# mbed-WiFi-Cloud-v1_0_0.net
KiCad netlist of a schematic drawn in EAGLE
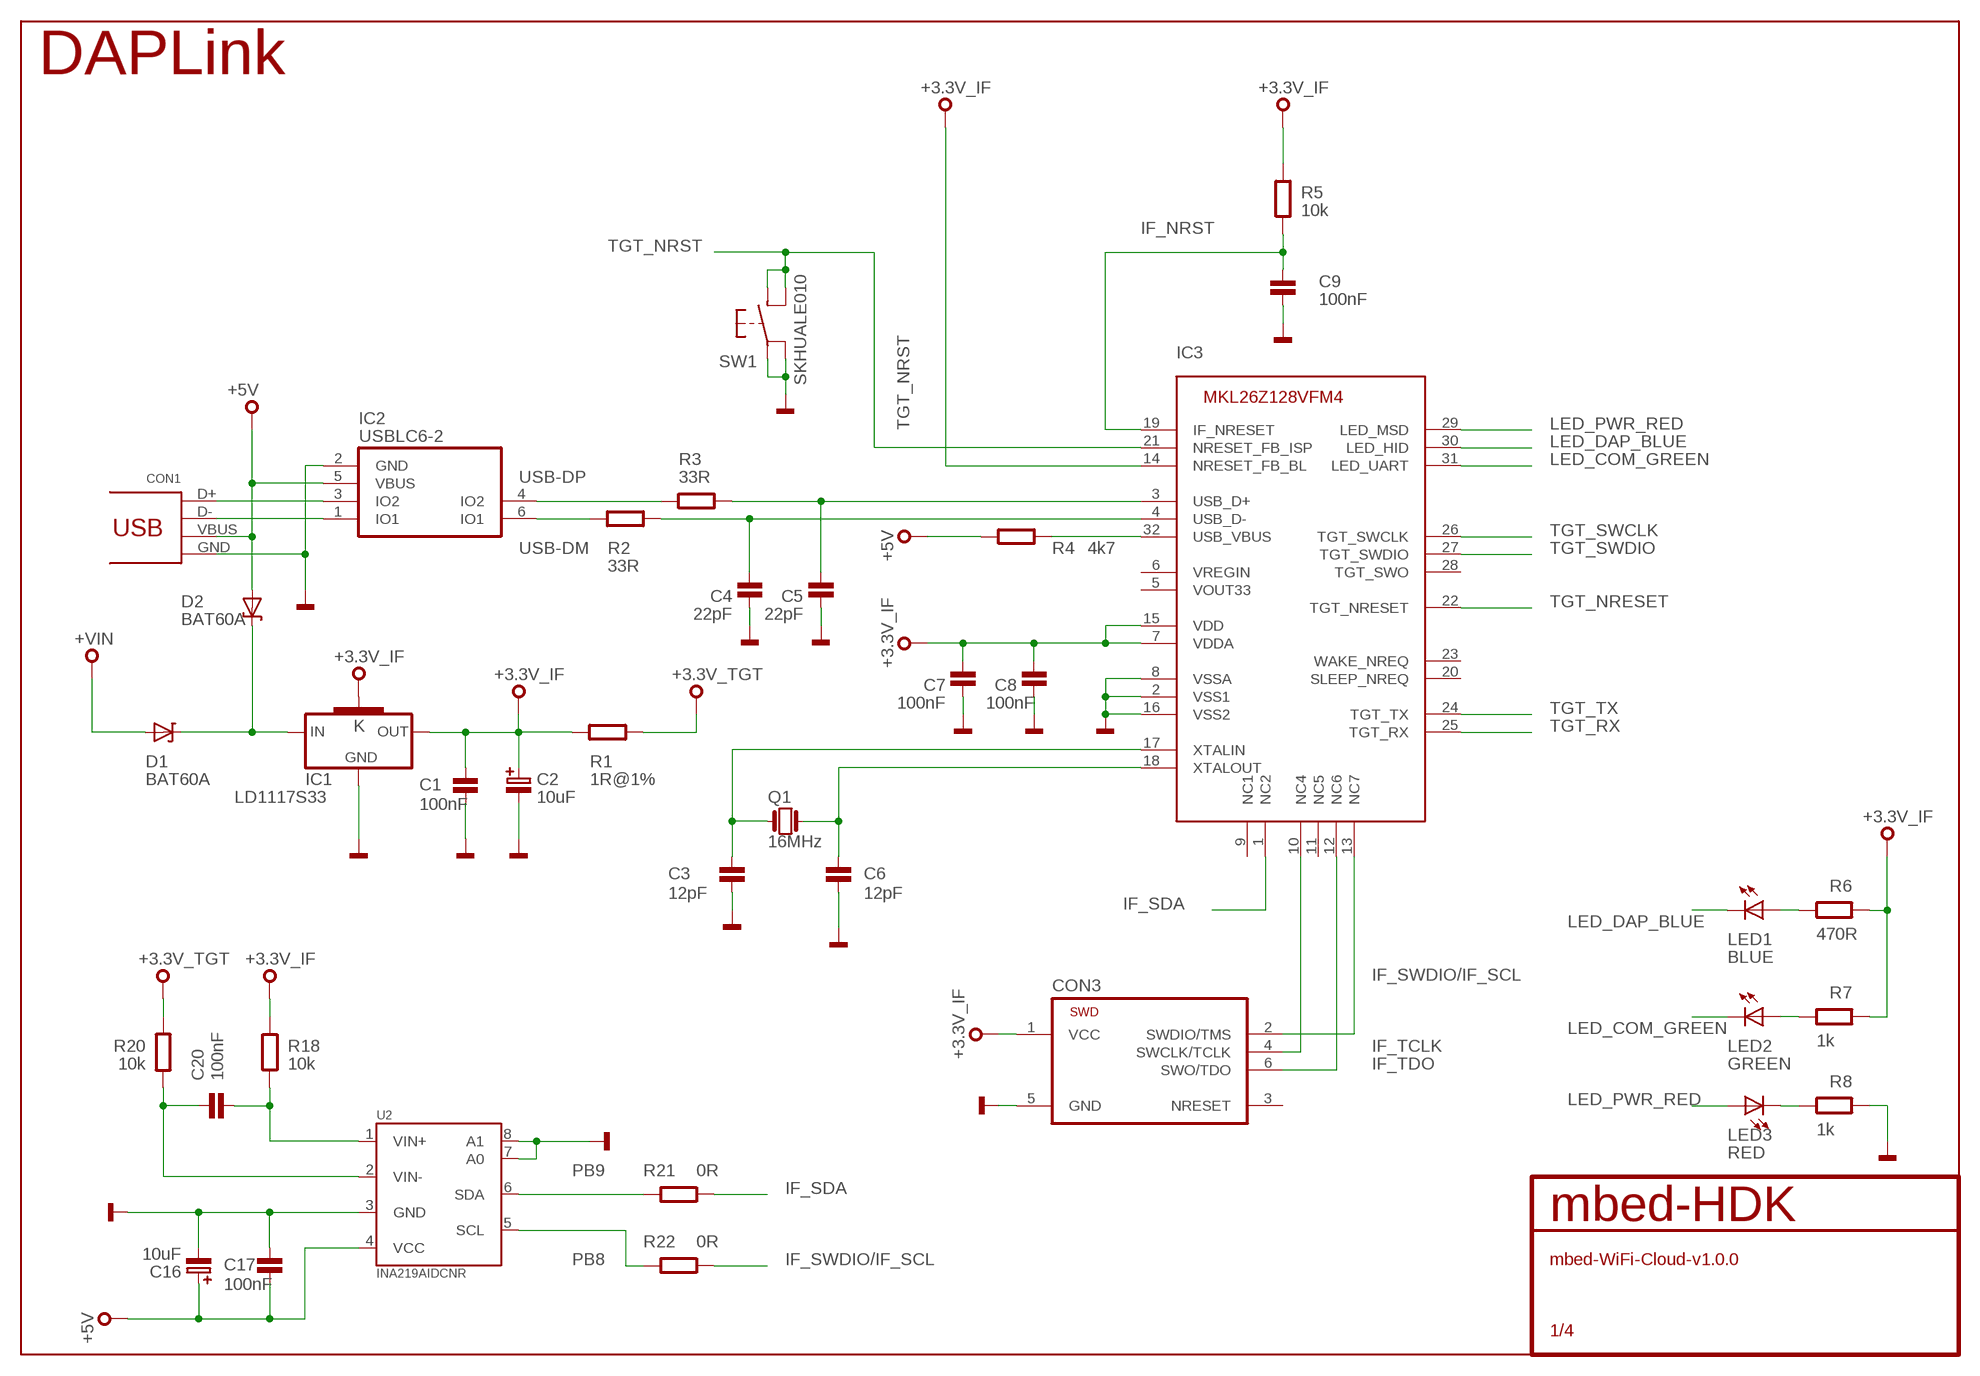
[diagram p0: schematic, sheet 1]
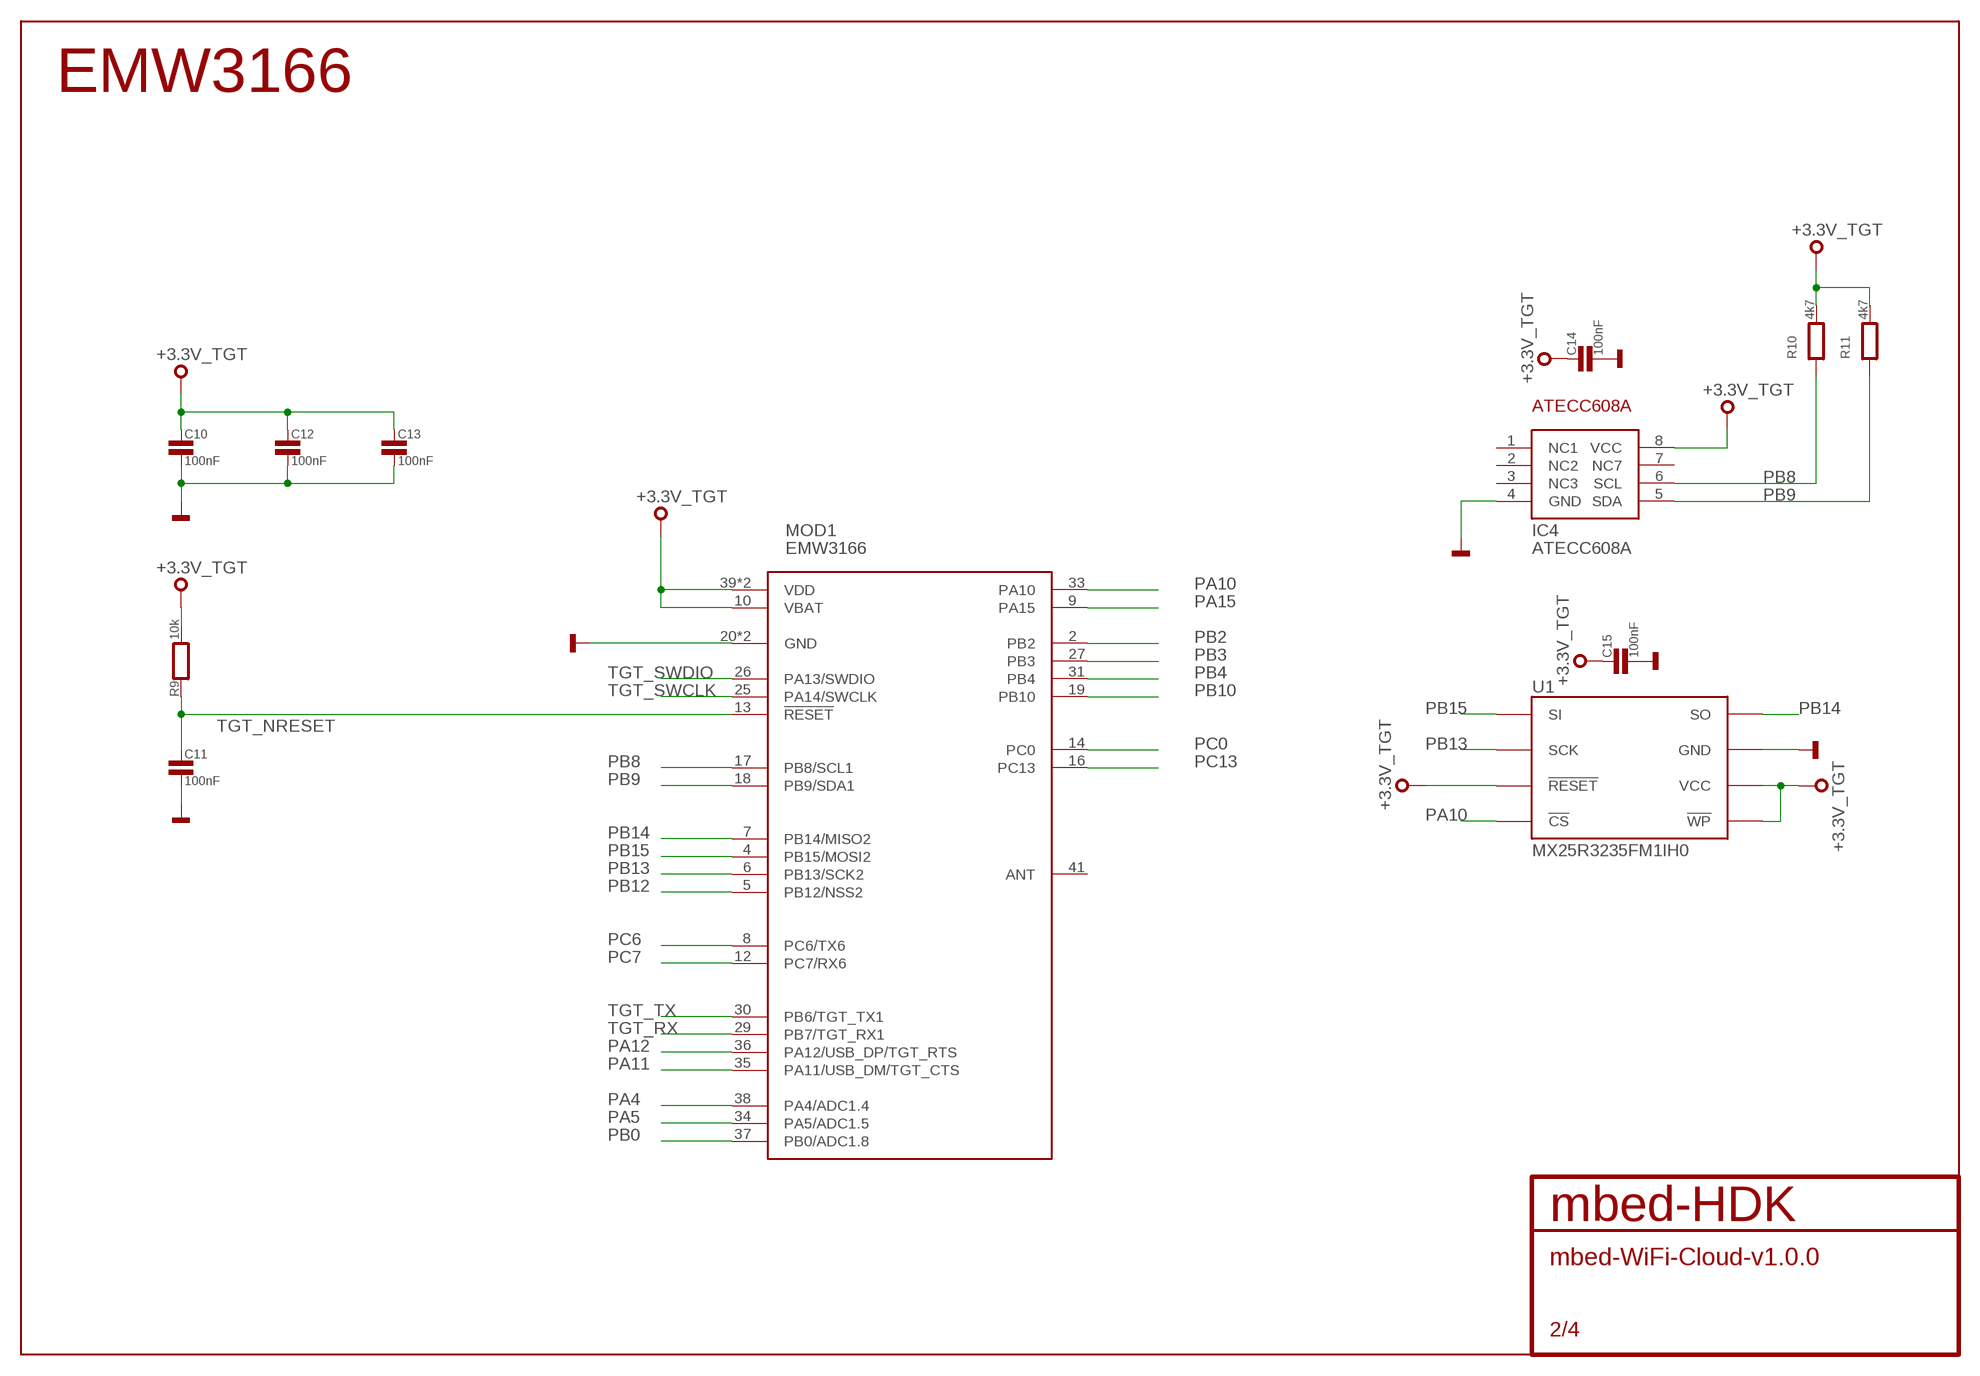
[diagram p1: schematic, sheet 2]
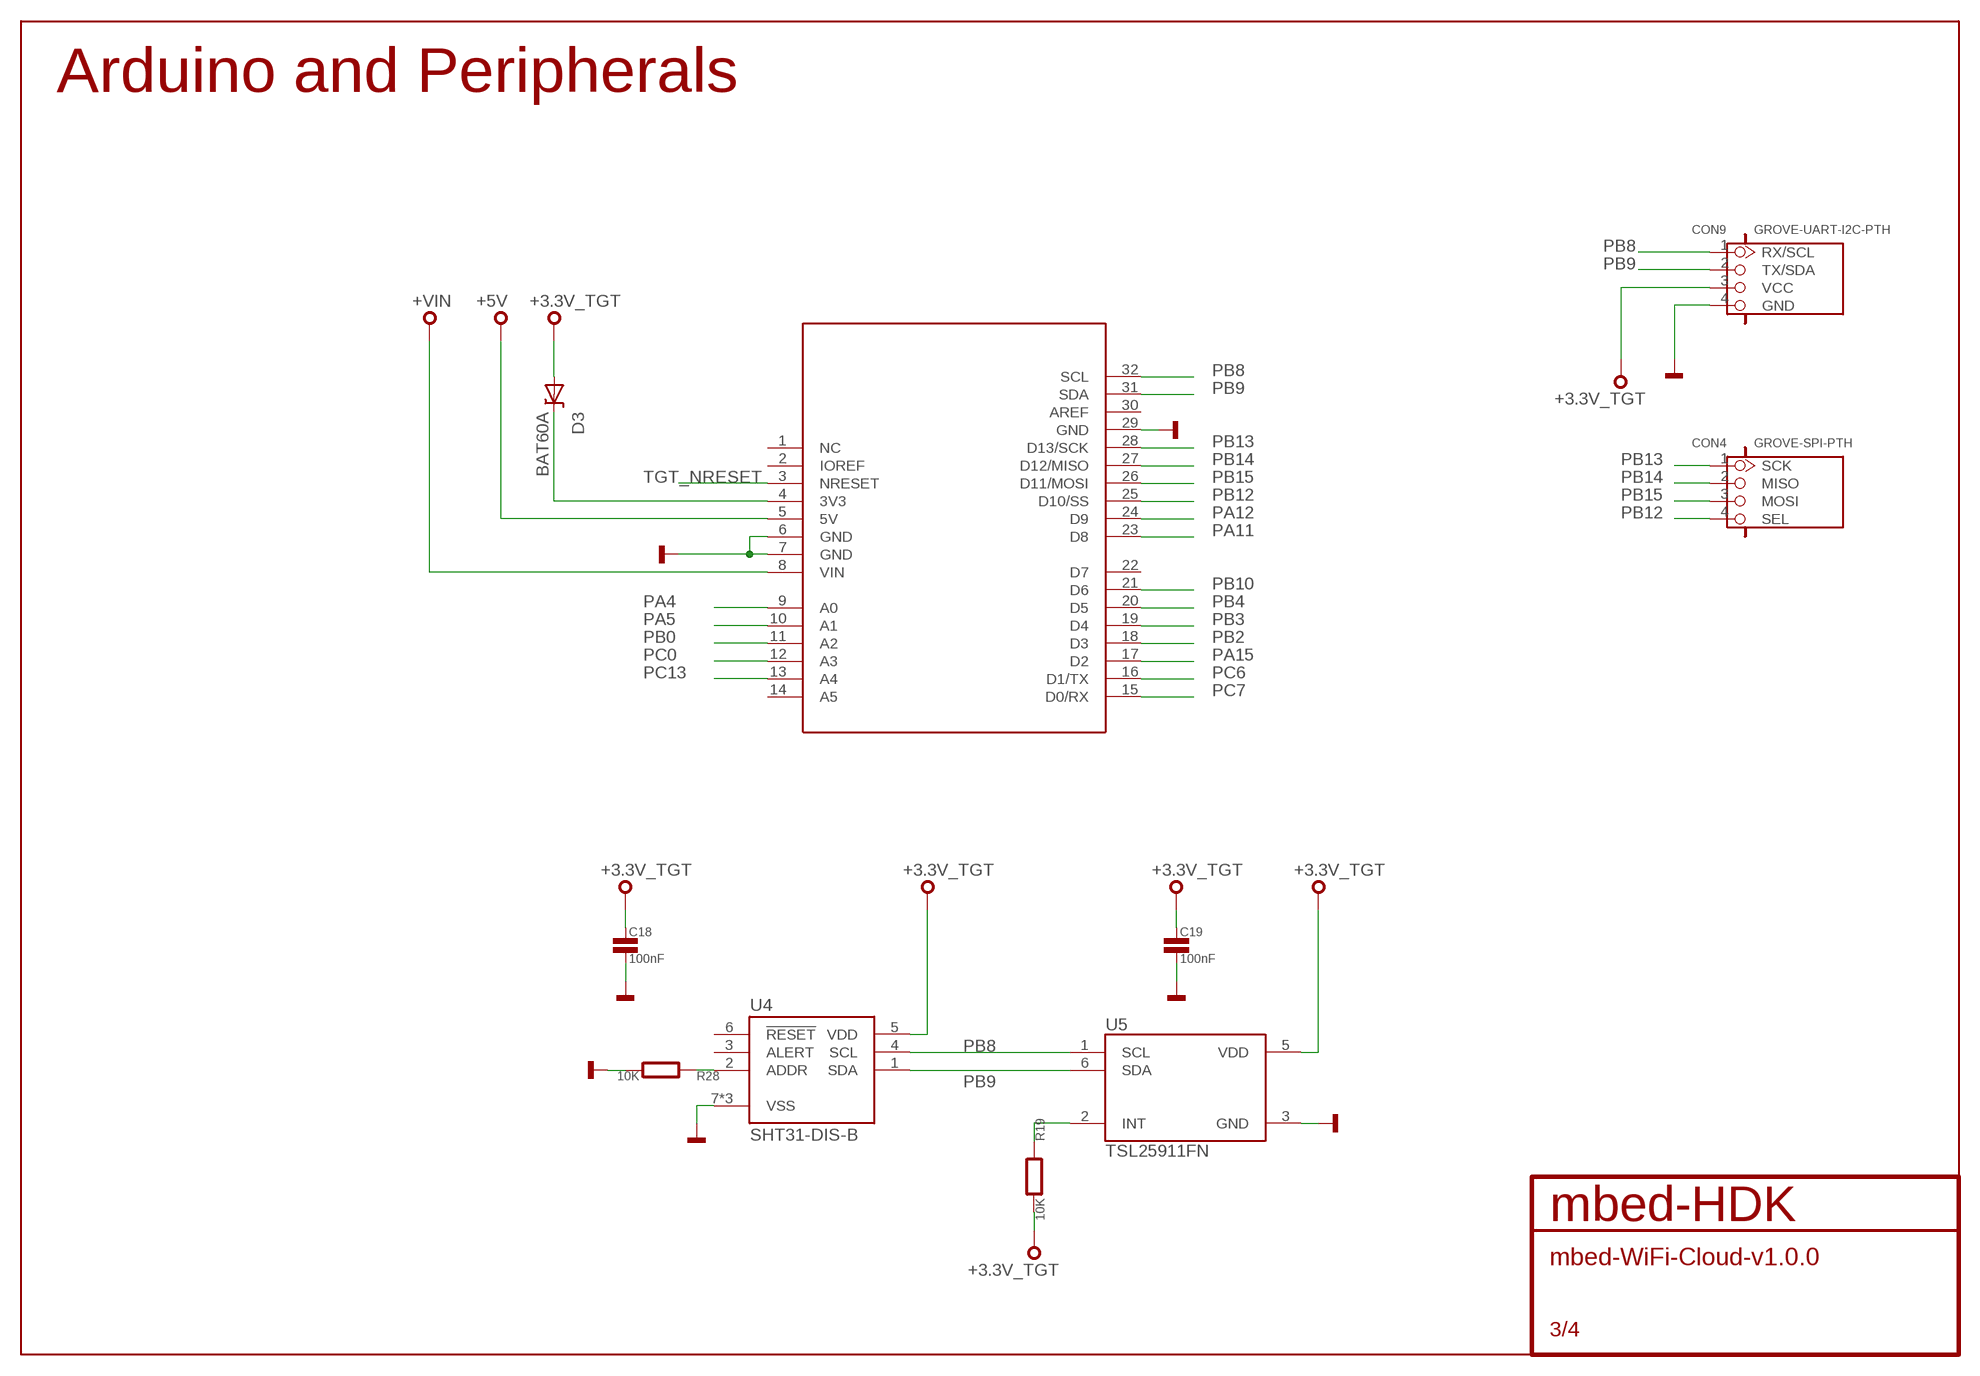
[diagram p2: schematic, sheet 3]
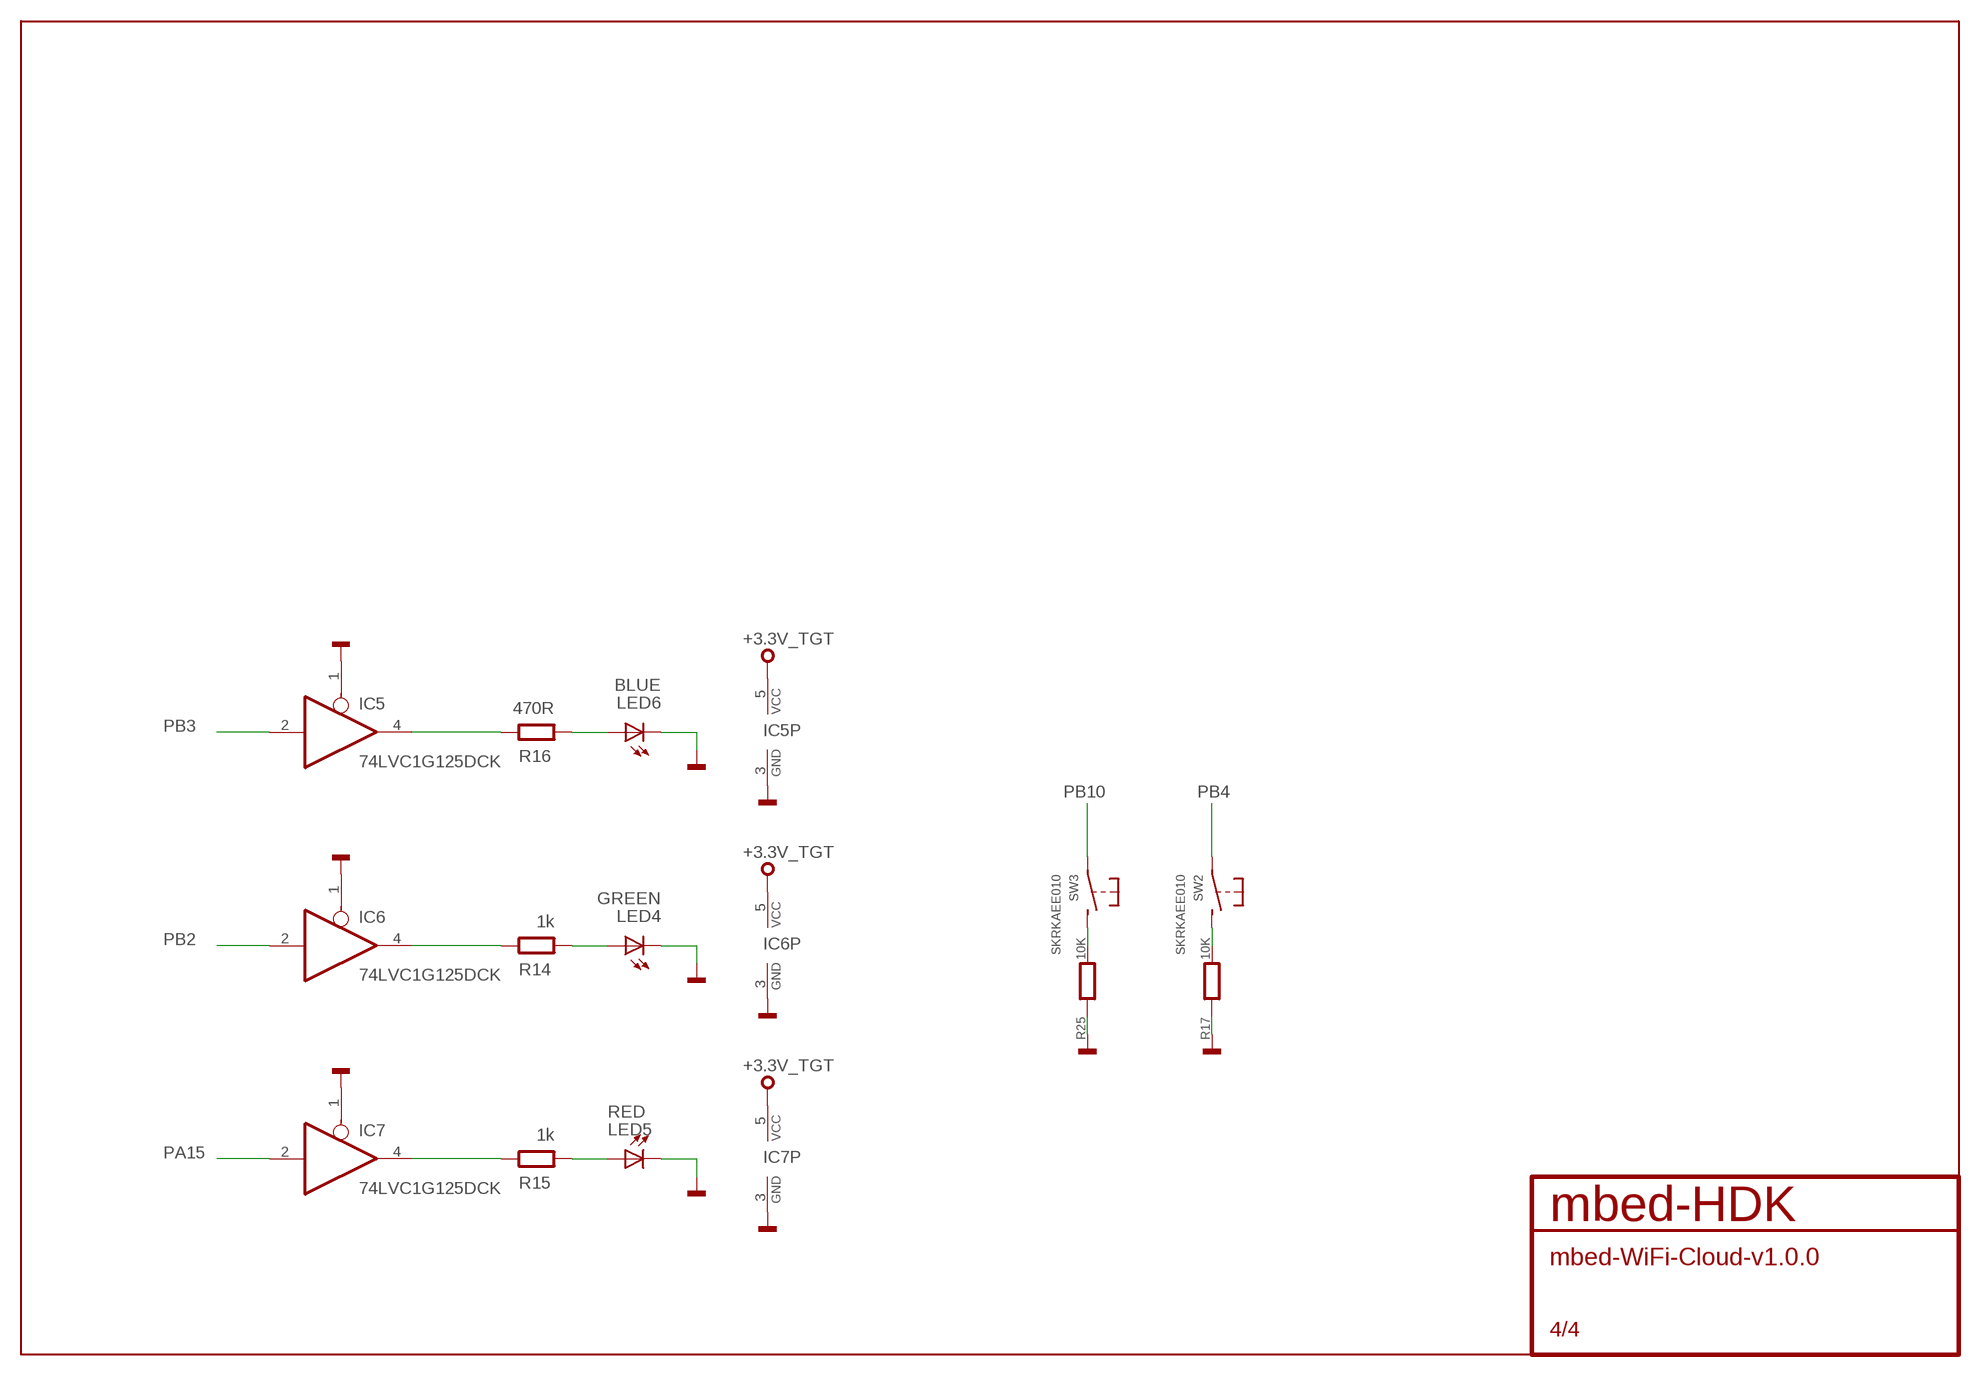
[diagram p3: schematic, sheet 4]

(export (version "E")
  (design (tool "Eeschema 10.0.6"))
  (components
    (comp (ref "C1")
      (value "100nF")
      (footprint "eagle-import:0603")
      (libsource (lib "eagle-import") (part "C0603"))
    )
    (comp (ref "C2")
      (value "10uF")
      (footprint "eagle-import:CASE-B")
      (libsource (lib "eagle-import") (part "C-POL_B"))
    )
    (comp (ref "C3")
      (value "12pF")
      (footprint "eagle-import:0603")
      (libsource (lib "eagle-import") (part "C0603"))
    )
    (comp (ref "C4")
      (value "22pF")
      (footprint "eagle-import:0603")
      (libsource (lib "eagle-import") (part "C0603"))
    )
    (comp (ref "C5")
      (value "22pF")
      (footprint "eagle-import:0603")
      (libsource (lib "eagle-import") (part "C0603"))
    )
    (comp (ref "C6")
      (value "12pF")
      (footprint "eagle-import:0603")
      (libsource (lib "eagle-import") (part "C0603"))
    )
    (comp (ref "C7")
      (value "100nF")
      (footprint "eagle-import:0603")
      (libsource (lib "eagle-import") (part "C0603"))
    )
    (comp (ref "C8")
      (value "100nF")
      (footprint "eagle-import:0603")
      (libsource (lib "eagle-import") (part "C0603"))
    )
    (comp (ref "C9")
      (value "100nF")
      (footprint "eagle-import:0603")
      (libsource (lib "eagle-import") (part "C0603"))
    )
    (comp (ref "C16")
      (value "10uF")
      (footprint "eagle-import:CASE-B")
      (libsource (lib "eagle-import") (part "C-POL_B"))
    )
    (comp (ref "C17")
      (value "100nF")
      (footprint "eagle-import:0603")
      (libsource (lib "eagle-import") (part "C0603"))
    )
    (comp (ref "C20")
      (value "100nF")
      (footprint "eagle-import:0603")
      (libsource (lib "eagle-import") (part "C0603"))
    )
    (comp (ref "CON1")
      (value "USB_MICROB")
      (footprint "eagle-import:MOLEX-47364-0001")
      (libsource (lib "eagle-import") (part "USB_MICROB"))
    )
    (comp (ref "CON3")
      (value "TC2030-CTX-NL")
      (footprint "eagle-import:TC2030-CTX-NL")
      (libsource (lib "eagle-import") (part "TC2030-CTX-NL"))
    )
    (comp (ref "D1")
      (value "BAT60A")
      (footprint "eagle-import:SOD323")
      (fields (field (name "MF") "Infineon"))
      (libsource (lib "eagle-import") (part "BAT60A"))
    )
    (comp (ref "D2")
      (value "BAT60A")
      (footprint "eagle-import:SOD323")
      (fields (field (name "MF") "Infineon"))
      (libsource (lib "eagle-import") (part "BAT60A"))
    )
    (comp (ref "IC1")
      (value "LD1117S33")
      (footprint "eagle-import:SOT223")
      (libsource (lib "eagle-import") (part "LD1117S33"))
    )
    (comp (ref "IC2")
      (value "USBLC6-2SC6")
      (footprint "eagle-import:SOT23-6L")
      (libsource (lib "eagle-import") (part "USBLC6-2SC6"))
    )
    (comp (ref "IC3")
      (value "IF_MKL26Z128VFM4")
      (footprint "eagle-import:HVQFN32")
      (libsource (lib "eagle-import") (part "IF_MKL26Z128VFM4"))
    )
    (comp (ref "LED1")
      (value "BLUE")
      (footprint "eagle-import:CHIPLED_0603")
      (libsource (lib "eagle-import") (part "LED0603"))
    )
    (comp (ref "LED2")
      (value "GREEN")
      (footprint "eagle-import:CHIPLED_0603")
      (libsource (lib "eagle-import") (part "LED0603"))
    )
    (comp (ref "LED3")
      (value "RED")
      (footprint "eagle-import:CHIPLED_0603")
      (libsource (lib "eagle-import") (part "LED0603"))
    )
    (comp (ref "Q1")
      (value "16MHz")
      (footprint "eagle-import:2.5X2.0")
      (libsource (lib "eagle-import") (part "Q_2.5X2.0"))
    )
    (comp (ref "R1")
      (value "1R@1%")
      (footprint "eagle-import:0603@1")
      (libsource (lib "eagle-import") (part "R0603"))
    )
    (comp (ref "R2")
      (value "33R")
      (footprint "eagle-import:0603@1")
      (libsource (lib "eagle-import") (part "R0603"))
    )
    (comp (ref "R3")
      (value "33R")
      (footprint "eagle-import:0603@1")
      (libsource (lib "eagle-import") (part "R0603"))
    )
    (comp (ref "R4")
      (value "4k7")
      (footprint "eagle-import:0603@1")
      (libsource (lib "eagle-import") (part "R0603"))
    )
    (comp (ref "R5")
      (value "10k")
      (footprint "eagle-import:0603@1")
      (libsource (lib "eagle-import") (part "R0603"))
    )
    (comp (ref "R6")
      (value "470R")
      (footprint "eagle-import:0603@1")
      (libsource (lib "eagle-import") (part "R0603"))
    )
    (comp (ref "R7")
      (value "1k")
      (footprint "eagle-import:0603@1")
      (libsource (lib "eagle-import") (part "R0603"))
    )
    (comp (ref "R8")
      (value "1k")
      (footprint "eagle-import:0603@1")
      (libsource (lib "eagle-import") (part "R0603"))
    )
    (comp (ref "R18")
      (value "10k")
      (footprint "eagle-import:0603@1")
      (libsource (lib "eagle-import") (part "R0603"))
    )
    (comp (ref "R20")
      (value "10k")
      (footprint "eagle-import:0603@1")
      (libsource (lib "eagle-import") (part "R0603"))
    )
    (comp (ref "R21")
      (value "0R")
      (footprint "eagle-import:0603@1")
      (libsource (lib "eagle-import") (part "R0603"))
    )
    (comp (ref "R22")
      (value "0R")
      (footprint "eagle-import:0603@1")
      (libsource (lib "eagle-import") (part "R0603"))
    )
    (comp (ref "SW1")
      (value "SKHUALE010")
      (footprint "eagle-import:SKHUALE010")
      (fields (field (name "MF") "ALPS"))
      (libsource (lib "eagle-import") (part "SKHUALE010"))
    )
    (comp (ref "U2")
      (value "INA219AIDCNR")
      (footprint "eagle-import:SOT23-8")
      (fields (field (name "MF") "Texas Instruments"))
      (libsource (lib "eagle-import") (part "INA219AIDCNR"))
    )
    (comp (ref "IC5")
      (value "74LVC1G125DCK")
      (footprint "eagle-import:SC70-5")
      (libsource (lib "eagle-import") (part "741G125DCKLVC"))
    )
    (comp (ref "IC6")
      (value "74LVC1G125DCK")
      (footprint "eagle-import:SC70-5")
      (libsource (lib "eagle-import") (part "741G125DCKLVC"))
    )
    (comp (ref "IC7")
      (value "74LVC1G125DCK")
      (footprint "eagle-import:SC70-5")
      (libsource (lib "eagle-import") (part "741G125DCKLVC"))
    )
    (comp (ref "LED4")
      (value "GREEN")
      (footprint "eagle-import:CHIPLED_0603")
      (libsource (lib "eagle-import") (part "LED0603"))
    )
    (comp (ref "LED5")
      (value "RED")
      (footprint "eagle-import:CHIPLED_0603")
      (libsource (lib "eagle-import") (part "LED0603"))
    )
    (comp (ref "LED6")
      (value "BLUE")
      (footprint "eagle-import:CHIPLED_0603")
      (libsource (lib "eagle-import") (part "LED0603"))
    )
    (comp (ref "R14")
      (value "1k")
      (footprint "eagle-import:0603@1")
      (libsource (lib "eagle-import") (part "R0603"))
    )
    (comp (ref "R15")
      (value "1k")
      (footprint "eagle-import:0603@1")
      (libsource (lib "eagle-import") (part "R0603"))
    )
    (comp (ref "R16")
      (value "470R")
      (footprint "eagle-import:0603@1")
      (libsource (lib "eagle-import") (part "R0603"))
    )
    (comp (ref "R17")
      (value "10K")
      (footprint "eagle-import:0603")
      (libsource (lib "eagle-import") (part "RESISTOR0603"))
    )
    (comp (ref "R25")
      (value "10K")
      (footprint "eagle-import:0603")
      (libsource (lib "eagle-import") (part "RESISTOR0603"))
    )
    (comp (ref "SW2")
      (value "SKRKAEE010")
      (footprint "eagle-import:SKRKAEE010")
      (fields (field (name "MF") "ALPS"))
      (libsource (lib "eagle-import") (part "SKRKAEE010"))
    )
    (comp (ref "SW3")
      (value "SKRKAEE010")
      (footprint "eagle-import:SKRKAEE010")
      (fields (field (name "MF") "ALPS"))
      (libsource (lib "eagle-import") (part "SKRKAEE010"))
    )
    (comp (ref "C10")
      (value "100nF")
      (footprint "eagle-import:0603")
      (libsource (lib "eagle-import") (part "CAPACITOR0603"))
    )
    (comp (ref "C11")
      (value "100nF")
      (footprint "eagle-import:0603")
      (libsource (lib "eagle-import") (part "CAPACITOR0603"))
    )
    (comp (ref "C12")
      (value "100nF")
      (footprint "eagle-import:0603")
      (libsource (lib "eagle-import") (part "CAPACITOR0603"))
    )
    (comp (ref "C13")
      (value "100nF")
      (footprint "eagle-import:0603")
      (libsource (lib "eagle-import") (part "CAPACITOR0603"))
    )
    (comp (ref "C14")
      (value "100nF")
      (footprint "eagle-import:0603")
      (libsource (lib "eagle-import") (part "CAPACITOR0603"))
    )
    (comp (ref "C15")
      (value "100nF")
      (footprint "eagle-import:0603")
      (libsource (lib "eagle-import") (part "CAPACITOR0603"))
    )
    (comp (ref "IC4")
      (value "ATECC608A")
      (footprint "eagle-import:SO8")
      (libsource (lib "eagle-import") (part "ATECC608A"))
    )
    (comp (ref "MOD1")
      (value "EMW3166")
      (footprint "eagle-import:EMW3166")
      (libsource (lib "eagle-import") (part "EMW3166"))
    )
    (comp (ref "R9")
      (value "10k")
      (footprint "eagle-import:0603")
      (libsource (lib "eagle-import") (part "RESISTOR0603"))
    )
    (comp (ref "R10")
      (value "4k7")
      (footprint "eagle-import:0603")
      (libsource (lib "eagle-import") (part "RESISTOR0603"))
    )
    (comp (ref "R11")
      (value "4k7")
      (footprint "eagle-import:0603")
      (libsource (lib "eagle-import") (part "RESISTOR0603"))
    )
    (comp (ref "U1")
      (value "MX25R3235FM1IH0")
      (footprint "eagle-import:SO8")
      (fields (field (name "MF") "Macronix"))
      (libsource (lib "eagle-import") (part "MX25R3235FM1IH0"))
    )
    (comp (ref "BRD1")
      (value "K64F/K22F-SHIELD")
      (footprint "eagle-import:K64F_K22F")
      (libsource (lib "eagle-import") (part "K64F/K22F-SHIELD"))
    )
    (comp (ref "C18")
      (value "100nF")
      (footprint "eagle-import:0603")
      (libsource (lib "eagle-import") (part "CAPACITOR0603"))
    )
    (comp (ref "C19")
      (value "100nF")
      (footprint "eagle-import:0603")
      (libsource (lib "eagle-import") (part "CAPACITOR0603"))
    )
    (comp (ref "CON4")
      (value "GROVE-SPI-PTH")
      (footprint "eagle-import:HW4-2.0")
      (libsource (lib "eagle-import") (part "GROVE-SPI-PTH"))
    )
    (comp (ref "CON9")
      (value "GROVE-UART-I2C-PTH")
      (footprint "eagle-import:HW4-2.0")
      (libsource (lib "eagle-import") (part "GROVE-UART-I2C-PTH"))
    )
    (comp (ref "D3")
      (value "BAT60A")
      (footprint "eagle-import:SOD323")
      (fields (field (name "MF") "Infineon"))
      (libsource (lib "eagle-import") (part "BAT60A"))
    )
    (comp (ref "R19")
      (value "10K")
      (footprint "eagle-import:0603")
      (libsource (lib "eagle-import") (part "RESISTOR0603"))
    )
    (comp (ref "R28")
      (value "10K")
      (footprint "eagle-import:0603")
      (libsource (lib "eagle-import") (part "RESISTOR0603"))
    )
    (comp (ref "U4")
      (value "SHT31-DIS-B")
      (footprint "eagle-import:8-DFN")
      (fields (field (name "MF") "Sensirion"))
      (libsource (lib "eagle-import") (part "SHT31-DIS-B"))
    )
    (comp (ref "U5")
      (value "TSL25911FN")
      (footprint "eagle-import:6-WFDFN")
      (fields (field (name "MF") "ams"))
      (libsource (lib "eagle-import") (part "TSL25911FN"))
    )
  )
  (nets
    (net (code "1") (name "+3.3V_IF") (class "Default")
      (node (ref "C1") (pin "1") (pinfunction "P$1_1") (pintype "passive"))
      (node (ref "C2") (pin "1") (pinfunction "1_1") (pintype "passive"))
      (node (ref "C7") (pin "2") (pinfunction "P$2_2") (pintype "passive"))
      (node (ref "C8") (pin "2") (pinfunction "P$2_2") (pintype "passive"))
      (node (ref "CON3") (pin "1") (pinfunction "VCC_1") (pintype "passive"))
      (node (ref "IC1") (pin "2") (pinfunction "OUT_2") (pintype "passive"))
      (node (ref "IC1") (pin "4") (pinfunction "K_4") (pintype "passive"))
      (node (ref "IC3") (pin "14") (pinfunction "NRESET_FB_BL_14") (pintype "bidirectional"))
      (node (ref "IC3") (pin "15") (pinfunction "VDD_15") (pintype "bidirectional"))
      (node (ref "IC3") (pin "7") (pinfunction "VDDA_7") (pintype "bidirectional"))
      (node (ref "R1") (pin "2") (pinfunction "P$2_2") (pintype "passive"))
      (node (ref "R18") (pin "2") (pinfunction "P$2_2") (pintype "passive"))
      (node (ref "R5") (pin "2") (pinfunction "P$2_2") (pintype "passive"))
      (node (ref "R6") (pin "1") (pinfunction "P$1_1") (pintype "passive"))
      (node (ref "R7") (pin "1") (pinfunction "P$1_1") (pintype "passive"))
    )
    (net (code "2") (name "+3.3V_TGT") (class "Default")
      (node (ref "C10") (pin "1") (pinfunction "P$1_1") (pintype "passive"))
      (node (ref "C12") (pin "1") (pinfunction "P$1_1") (pintype "passive"))
      (node (ref "C13") (pin "1") (pinfunction "P$1_1") (pintype "passive"))
      (node (ref "C14") (pin "1") (pinfunction "P$1_1") (pintype "passive"))
      (node (ref "C15") (pin "1") (pinfunction "P$1_1") (pintype "passive"))
      (node (ref "C18") (pin "1") (pinfunction "P$1_1") (pintype "passive"))
      (node (ref "C19") (pin "1") (pinfunction "P$1_1") (pintype "passive"))
      (node (ref "CON9") (pin "3") (pinfunction "VCC_3") (pintype "bidirectional"))
      (node (ref "D3") (pin "A") (pinfunction "A_A") (pintype "passive"))
      (node (ref "IC4") (pin "8") (pinfunction "VCC_8") (pintype "bidirectional"))
      (node (ref "IC5") (pin "5") (pinfunction "VCC_5") (pintype "power_in"))
      (node (ref "IC6") (pin "5") (pinfunction "VCC_5") (pintype "power_in"))
      (node (ref "IC7") (pin "5") (pinfunction "VCC_5") (pintype "power_in"))
      (node (ref "MOD1") (pin "10") (pinfunction "VBAT_10") (pintype "bidirectional"))
      (node (ref "MOD1") (pin "39") (pinfunction "VDD_39") (pintype "bidirectional"))
      (node (ref "MOD1") (pin "40") (pinfunction "VDD_40") (pintype "bidirectional"))
      (node (ref "R1") (pin "1") (pinfunction "P$1_1") (pintype "passive"))
      (node (ref "R10") (pin "2") (pinfunction "P$2_2") (pintype "passive"))
      (node (ref "R11") (pin "2") (pinfunction "P$2_2") (pintype "passive"))
      (node (ref "R19") (pin "2") (pinfunction "P$2_2") (pintype "passive"))
      (node (ref "R20") (pin "2") (pinfunction "P$2_2") (pintype "passive"))
      (node (ref "R9") (pin "2") (pinfunction "P$2_2") (pintype "passive"))
      (node (ref "U1") (pin "3") (pinfunction "~{WP}_3") (pintype "bidirectional"))
      (node (ref "U1") (pin "7") (pinfunction "~{RESET}_7") (pintype "bidirectional"))
      (node (ref "U1") (pin "8") (pinfunction "VCC_8") (pintype "bidirectional"))
      (node (ref "U4") (pin "5") (pinfunction "VDD_5") (pintype "bidirectional"))
      (node (ref "U5") (pin "5") (pinfunction "VDD_5") (pintype "bidirectional"))
    )
    (net (code "3") (name "+5V") (class "Default")
      (node (ref "BRD1") (pin "5") (pinfunction "5V_5") (pintype "bidirectional"))
      (node (ref "C16") (pin "1") (pinfunction "1_1") (pintype "passive"))
      (node (ref "C17") (pin "2") (pinfunction "P$2_2") (pintype "passive"))
      (node (ref "CON1") (pin "VBUS") (pinfunction "VBUS_VBUS") (pintype "bidirectional"))
      (node (ref "D2") (pin "A") (pinfunction "A_A") (pintype "passive"))
      (node (ref "IC2") (pin "5") (pinfunction "VBUS_5") (pintype "bidirectional"))
      (node (ref "R4") (pin "1") (pinfunction "P$1_1") (pintype "passive"))
      (node (ref "U2") (pin "4") (pinfunction "VCC_4") (pintype "power_in"))
    )
    (net (code "4") (name "+VIN") (class "Default")
      (node (ref "BRD1") (pin "8") (pinfunction "VIN_8") (pintype "bidirectional"))
      (node (ref "D1") (pin "A") (pinfunction "A_A") (pintype "passive"))
    )
    (net (code "5") (name "GND") (class "Default")
      (node (ref "BRD1") (pin "29") (pinfunction "GND_29") (pintype "bidirectional"))
      (node (ref "BRD1") (pin "6") (pinfunction "GND_6") (pintype "bidirectional"))
      (node (ref "BRD1") (pin "7") (pinfunction "GND_7") (pintype "bidirectional"))
      (node (ref "C1") (pin "2") (pinfunction "P$2_2") (pintype "passive"))
      (node (ref "C10") (pin "2") (pinfunction "P$2_2") (pintype "passive"))
      (node (ref "C11") (pin "2") (pinfunction "P$2_2") (pintype "passive"))
      (node (ref "C12") (pin "2") (pinfunction "P$2_2") (pintype "passive"))
      (node (ref "C13") (pin "2") (pinfunction "P$2_2") (pintype "passive"))
      (node (ref "C14") (pin "2") (pinfunction "P$2_2") (pintype "passive"))
      (node (ref "C15") (pin "2") (pinfunction "P$2_2") (pintype "passive"))
      (node (ref "C16") (pin "2") (pinfunction "2_2") (pintype "passive"))
      (node (ref "C17") (pin "1") (pinfunction "P$1_1") (pintype "passive"))
      (node (ref "C18") (pin "2") (pinfunction "P$2_2") (pintype "passive"))
      (node (ref "C19") (pin "2") (pinfunction "P$2_2") (pintype "passive"))
      (node (ref "C2") (pin "2") (pinfunction "2_2") (pintype "passive"))
      (node (ref "C3") (pin "1") (pinfunction "P$1_1") (pintype "passive"))
      (node (ref "C4") (pin "1") (pinfunction "P$1_1") (pintype "passive"))
      (node (ref "C5") (pin "1") (pinfunction "P$1_1") (pintype "passive"))
      (node (ref "C6") (pin "1") (pinfunction "P$1_1") (pintype "passive"))
      (node (ref "C7") (pin "1") (pinfunction "P$1_1") (pintype "passive"))
      (node (ref "C8") (pin "1") (pinfunction "P$1_1") (pintype "passive"))
      (node (ref "C9") (pin "1") (pinfunction "P$1_1") (pintype "passive"))
      (node (ref "CON1") (pin "GND") (pinfunction "GND_GND") (pintype "bidirectional"))
      (node (ref "CON3") (pin "5") (pinfunction "GND_5") (pintype "passive"))
      (node (ref "CON9") (pin "4") (pinfunction "GND_4") (pintype "bidirectional"))
      (node (ref "IC1") (pin "1") (pinfunction "GND_1") (pintype "input"))
      (node (ref "IC2") (pin "2") (pinfunction "GND_2") (pintype "bidirectional"))
      (node (ref "IC3") (pin "16") (pinfunction "VSS2_16") (pintype "bidirectional"))
      (node (ref "IC3") (pin "2") (pinfunction "VSS1_2") (pintype "bidirectional"))
      (node (ref "IC3") (pin "8") (pinfunction "VSSA_8") (pintype "bidirectional"))
      (node (ref "IC4") (pin "4") (pinfunction "GND_4") (pintype "bidirectional"))
      (node (ref "IC5") (pin "1") (pinfunction "OE_1") (pintype "input"))
      (node (ref "IC5") (pin "3") (pinfunction "GND_3") (pintype "power_in"))
      (node (ref "IC6") (pin "1") (pinfunction "OE_1") (pintype "input"))
      (node (ref "IC6") (pin "3") (pinfunction "GND_3") (pintype "power_in"))
      (node (ref "IC7") (pin "1") (pinfunction "OE_1") (pintype "input"))
      (node (ref "IC7") (pin "3") (pinfunction "GND_3") (pintype "power_in"))
      (node (ref "LED4") (pin "C") (pinfunction "C_C") (pintype "passive"))
      (node (ref "LED5") (pin "C") (pinfunction "C_C") (pintype "passive"))
      (node (ref "LED6") (pin "C") (pinfunction "C_C") (pintype "passive"))
      (node (ref "MOD1") (pin "20") (pinfunction "GND_20") (pintype "bidirectional"))
      (node (ref "MOD1") (pin "21") (pinfunction "GND_21") (pintype "bidirectional"))
      (node (ref "R17") (pin "1") (pinfunction "P$1_1") (pintype "passive"))
      (node (ref "R25") (pin "1") (pinfunction "P$1_1") (pintype "passive"))
      (node (ref "R28") (pin "2") (pinfunction "P$2_2") (pintype "passive"))
      (node (ref "R8") (pin "1") (pinfunction "P$1_1") (pintype "passive"))
      (node (ref "SW1") (pin "P$1") (pinfunction "A1_P$1") (pintype "passive"))
      (node (ref "SW1") (pin "P$2") (pinfunction "A2_P$2") (pintype "passive"))
      (node (ref "U1") (pin "4") (pinfunction "GND_4") (pintype "bidirectional"))
      (node (ref "U2") (pin "3") (pinfunction "GND_3") (pintype "power_in"))
      (node (ref "U2") (pin "7") (pinfunction "A0_7") (pintype "input"))
      (node (ref "U2") (pin "8") (pinfunction "A1_8") (pintype "input"))
      (node (ref "U4") (pin "7") (pinfunction "VSS_7") (pintype "bidirectional"))
      (node (ref "U4") (pin "8") (pinfunction "VSS_8") (pintype "bidirectional"))
      (node (ref "U4") (pin "9") (pinfunction "VSS_9") (pintype "bidirectional"))
      (node (ref "U5") (pin "3") (pinfunction "GND_3") (pintype "bidirectional"))
    )
    (net (code "6") (name "IF_NRST") (class "Default")
      (node (ref "C9") (pin "2") (pinfunction "P$2_2") (pintype "passive"))
      (node (ref "IC3") (pin "19") (pinfunction "IF_NRESET_19") (pintype "bidirectional"))
      (node (ref "R5") (pin "1") (pinfunction "P$1_1") (pintype "passive"))
    )
    (net (code "7") (name "IF_SDA") (class "Default")
      (node (ref "IC3") (pin "1") (pinfunction "NC2_1") (pintype "bidirectional"))
      (node (ref "R21") (pin "1") (pinfunction "P$1_1") (pintype "passive"))
    )
    (net (code "8") (name "IF_SWDIO{slash}IF_SCL") (class "Default")
      (node (ref "CON3") (pin "2") (pinfunction "SWDIO/TMS_2") (pintype "passive"))
      (node (ref "IC3") (pin "13") (pinfunction "NC7_13") (pintype "bidirectional"))
      (node (ref "R22") (pin "1") (pinfunction "P$1_1") (pintype "passive"))
    )
    (net (code "9") (name "IF_TCLK") (class "Default")
      (node (ref "CON3") (pin "4") (pinfunction "SWCLK/TCLK_4") (pintype "passive"))
      (node (ref "IC3") (pin "10") (pinfunction "NC4_10") (pintype "bidirectional"))
    )
    (net (code "10") (name "IF_TDO") (class "Default")
      (node (ref "CON3") (pin "6") (pinfunction "SWO/TDO_6") (pintype "passive"))
      (node (ref "IC3") (pin "12") (pinfunction "NC6_12") (pintype "bidirectional"))
    )
    (net (code "11") (name "LED_COM_GREEN") (class "Default")
      (node (ref "IC3") (pin "31") (pinfunction "LED_UART_31") (pintype "bidirectional"))
      (node (ref "LED2") (pin "C") (pinfunction "C_C") (pintype "passive"))
    )
    (net (code "12") (name "LED_DAP_BLUE") (class "Default")
      (node (ref "IC3") (pin "30") (pinfunction "LED_HID_30") (pintype "bidirectional"))
      (node (ref "LED1") (pin "C") (pinfunction "C_C") (pintype "passive"))
    )
    (net (code "13") (name "LED_PWR_RED") (class "Default")
      (node (ref "IC3") (pin "29") (pinfunction "LED_MSD_29") (pintype "bidirectional"))
      (node (ref "LED3") (pin "A") (pinfunction "A_A") (pintype "passive"))
    )
    (net (code "14") (name "Net-(BRD1-3V3)") (class "Default")
      (node (ref "BRD1") (pin "4") (pinfunction "3V3_4") (pintype "bidirectional"))
      (node (ref "D3") (pin "K") (pinfunction "K_K") (pintype "passive"))
    )
    (net (code "15") (name "Net-(C3-P$2)") (class "Default")
      (node (ref "C3") (pin "2") (pinfunction "P$2_2") (pintype "passive"))
      (node (ref "IC3") (pin "17") (pinfunction "XTALIN_17") (pintype "bidirectional"))
      (node (ref "Q1") (pin "1") (pinfunction "1_1") (pintype "passive"))
    )
    (net (code "16") (name "Net-(C4-P$2)") (class "Default")
      (node (ref "C4") (pin "2") (pinfunction "P$2_2") (pintype "passive"))
      (node (ref "IC3") (pin "4") (pinfunction "USB_D-_4") (pintype "bidirectional"))
      (node (ref "R2") (pin "1") (pinfunction "P$1_1") (pintype "passive"))
    )
    (net (code "17") (name "Net-(C5-P$2)") (class "Default")
      (node (ref "C5") (pin "2") (pinfunction "P$2_2") (pintype "passive"))
      (node (ref "IC3") (pin "3") (pinfunction "USB_D+_3") (pintype "bidirectional"))
      (node (ref "R3") (pin "1") (pinfunction "P$1_1") (pintype "passive"))
    )
    (net (code "18") (name "Net-(C6-P$2)") (class "Default")
      (node (ref "C6") (pin "2") (pinfunction "P$2_2") (pintype "passive"))
      (node (ref "IC3") (pin "18") (pinfunction "XTALOUT_18") (pintype "bidirectional"))
      (node (ref "Q1") (pin "3") (pinfunction "2_3") (pintype "passive"))
    )
    (net (code "19") (name "Net-(C20-P$1)") (class "Default")
      (node (ref "C20") (pin "1") (pinfunction "P$1_1") (pintype "passive"))
      (node (ref "R18") (pin "1") (pinfunction "P$1_1") (pintype "passive"))
      (node (ref "U2") (pin "1") (pinfunction "VIN+_1") (pintype "input"))
    )
    (net (code "20") (name "Net-(C20-P$2)") (class "Default")
      (node (ref "C20") (pin "2") (pinfunction "P$2_2") (pintype "passive"))
      (node (ref "R20") (pin "1") (pinfunction "P$1_1") (pintype "passive"))
      (node (ref "U2") (pin "2") (pinfunction "VIN-_2") (pintype "input"))
    )
    (net (code "21") (name "Net-(CON1-PadD+)") (class "Default")
      (node (ref "CON1") (pin "D+") (pinfunction "D+_D+") (pintype "bidirectional"))
      (node (ref "IC2") (pin "3") (pinfunction "IO2_3") (pintype "bidirectional"))
    )
    (net (code "22") (name "Net-(CON1-PadD-)") (class "Default")
      (node (ref "CON1") (pin "D-") (pinfunction "D-_D-") (pintype "bidirectional"))
      (node (ref "IC2") (pin "1") (pinfunction "IO1_1") (pintype "bidirectional"))
    )
    (net (code "23") (name "Net-(IC1-IN)") (class "Default")
      (node (ref "D1") (pin "K") (pinfunction "K_K") (pintype "passive"))
      (node (ref "D2") (pin "K") (pinfunction "K_K") (pintype "passive"))
      (node (ref "IC1") (pin "3") (pinfunction "IN_3") (pintype "input"))
    )
    (net (code "24") (name "Net-(IC3-USB_VBUS)") (class "Default")
      (node (ref "IC3") (pin "32") (pinfunction "USB_VBUS_32") (pintype "bidirectional"))
      (node (ref "R4") (pin "2") (pinfunction "P$2_2") (pintype "passive"))
    )
    (net (code "25") (name "Net-(IC5A-O)") (class "Default")
      (node (ref "IC5") (pin "4") (pinfunction "O_4") (pintype "tri_state"))
      (node (ref "R16") (pin "1") (pinfunction "P$1_1") (pintype "passive"))
    )
    (net (code "26") (name "Net-(IC6A-O)") (class "Default")
      (node (ref "IC6") (pin "4") (pinfunction "O_4") (pintype "tri_state"))
      (node (ref "R14") (pin "1") (pinfunction "P$1_1") (pintype "passive"))
    )
    (net (code "27") (name "Net-(IC7A-O)") (class "Default")
      (node (ref "IC7") (pin "4") (pinfunction "O_4") (pintype "tri_state"))
      (node (ref "R15") (pin "1") (pinfunction "P$1_1") (pintype "passive"))
    )
    (net (code "28") (name "Net-(R6-P$2)") (class "Default")
      (node (ref "LED1") (pin "A") (pinfunction "A_A") (pintype "passive"))
      (node (ref "R6") (pin "2") (pinfunction "P$2_2") (pintype "passive"))
    )
    (net (code "29") (name "Net-(R7-P$2)") (class "Default")
      (node (ref "LED2") (pin "A") (pinfunction "A_A") (pintype "passive"))
      (node (ref "R7") (pin "2") (pinfunction "P$2_2") (pintype "passive"))
    )
    (net (code "30") (name "Net-(R8-P$2)") (class "Default")
      (node (ref "LED3") (pin "C") (pinfunction "C_C") (pintype "passive"))
      (node (ref "R8") (pin "2") (pinfunction "P$2_2") (pintype "passive"))
    )
    (net (code "31") (name "Net-(R14-P$2)") (class "Default")
      (node (ref "LED4") (pin "A") (pinfunction "A_A") (pintype "passive"))
      (node (ref "R14") (pin "2") (pinfunction "P$2_2") (pintype "passive"))
    )
    (net (code "32") (name "Net-(R15-P$2)") (class "Default")
      (node (ref "LED5") (pin "A") (pinfunction "A_A") (pintype "passive"))
      (node (ref "R15") (pin "2") (pinfunction "P$2_2") (pintype "passive"))
    )
    (net (code "33") (name "Net-(R16-P$2)") (class "Default")
      (node (ref "LED6") (pin "A") (pinfunction "A_A") (pintype "passive"))
      (node (ref "R16") (pin "2") (pinfunction "P$2_2") (pintype "passive"))
    )
    (net (code "34") (name "Net-(R17-P$2)") (class "Default")
      (node (ref "R17") (pin "2") (pinfunction "P$2_2") (pintype "passive"))
      (node (ref "SW2") (pin "P$2") (pinfunction "S_P$2") (pintype "passive"))
    )
    (net (code "35") (name "Net-(R19-P$1)") (class "Default")
      (node (ref "R19") (pin "1") (pinfunction "P$1_1") (pintype "passive"))
      (node (ref "U5") (pin "2") (pinfunction "INT_2") (pintype "bidirectional"))
    )
    (net (code "36") (name "Net-(R25-P$2)") (class "Default")
      (node (ref "R25") (pin "2") (pinfunction "P$2_2") (pintype "passive"))
      (node (ref "SW3") (pin "P$2") (pinfunction "S_P$2") (pintype "passive"))
    )
    (net (code "37") (name "Net-(R28-P$1)") (class "Default")
      (node (ref "R28") (pin "1") (pinfunction "P$1_1") (pintype "passive"))
      (node (ref "U4") (pin "2") (pinfunction "ADDR_2") (pintype "bidirectional"))
    )
    (net (code "38") (name "PA4") (class "Default")
      (node (ref "BRD1") (pin "9") (pinfunction "A0_9") (pintype "bidirectional"))
      (node (ref "MOD1") (pin "38") (pinfunction "PA4/ADC1.4_38") (pintype "bidirectional"))
    )
    (net (code "39") (name "PA5") (class "Default")
      (node (ref "BRD1") (pin "10") (pinfunction "A1_10") (pintype "bidirectional"))
      (node (ref "MOD1") (pin "34") (pinfunction "PA5/ADC1.5_34") (pintype "bidirectional"))
    )
    (net (code "40") (name "PA10") (class "Default")
      (node (ref "MOD1") (pin "33") (pinfunction "PA10_33") (pintype "bidirectional"))
      (node (ref "U1") (pin "1") (pinfunction "~{CS}_1") (pintype "bidirectional"))
    )
    (net (code "41") (name "PA11") (class "Default")
      (node (ref "BRD1") (pin "23") (pinfunction "D8_23") (pintype "bidirectional"))
      (node (ref "MOD1") (pin "35") (pinfunction "PA11/USB_DM/TGT_CTS_35") (pintype "bidirectional"))
    )
    (net (code "42") (name "PA12") (class "Default")
      (node (ref "BRD1") (pin "24") (pinfunction "D9_24") (pintype "bidirectional"))
      (node (ref "MOD1") (pin "36") (pinfunction "PA12/USB_DP/TGT_RTS_36") (pintype "bidirectional"))
    )
    (net (code "43") (name "PA15") (class "Default")
      (node (ref "BRD1") (pin "17") (pinfunction "D2_17") (pintype "bidirectional"))
      (node (ref "IC7") (pin "2") (pinfunction "I_2") (pintype "input"))
      (node (ref "MOD1") (pin "9") (pinfunction "PA15_9") (pintype "bidirectional"))
    )
    (net (code "44") (name "PB0") (class "Default")
      (node (ref "BRD1") (pin "11") (pinfunction "A2_11") (pintype "bidirectional"))
      (node (ref "MOD1") (pin "37") (pinfunction "PB0/ADC1.8_37") (pintype "bidirectional"))
    )
    (net (code "45") (name "PB2") (class "Default")
      (node (ref "BRD1") (pin "18") (pinfunction "D3_18") (pintype "bidirectional"))
      (node (ref "IC6") (pin "2") (pinfunction "I_2") (pintype "input"))
      (node (ref "MOD1") (pin "2") (pinfunction "PB2_2") (pintype "bidirectional"))
    )
    (net (code "46") (name "PB3") (class "Default")
      (node (ref "BRD1") (pin "19") (pinfunction "D4_19") (pintype "bidirectional"))
      (node (ref "IC5") (pin "2") (pinfunction "I_2") (pintype "input"))
      (node (ref "MOD1") (pin "27") (pinfunction "PB3_27") (pintype "bidirectional"))
    )
    (net (code "47") (name "PB4") (class "Default")
      (node (ref "BRD1") (pin "20") (pinfunction "D5_20") (pintype "bidirectional"))
      (node (ref "MOD1") (pin "31") (pinfunction "PB4_31") (pintype "bidirectional"))
      (node (ref "SW2") (pin "P$1") (pinfunction "P_P$1") (pintype "passive"))
    )
    (net (code "48") (name "PB8") (class "Default")
      (node (ref "BRD1") (pin "32") (pinfunction "SCL_32") (pintype "bidirectional"))
      (node (ref "CON9") (pin "1") (pinfunction "RX/SCL_1") (pintype "bidirectional"))
      (node (ref "IC4") (pin "6") (pinfunction "SCL_6") (pintype "bidirectional"))
      (node (ref "MOD1") (pin "17") (pinfunction "PB8/SCL1_17") (pintype "bidirectional"))
      (node (ref "R10") (pin "1") (pinfunction "P$1_1") (pintype "passive"))
      (node (ref "R22") (pin "2") (pinfunction "P$2_2") (pintype "passive"))
      (node (ref "U2") (pin "5") (pinfunction "SCL_5") (pintype "bidirectional"))
      (node (ref "U4") (pin "4") (pinfunction "SCL_4") (pintype "bidirectional"))
      (node (ref "U5") (pin "1") (pinfunction "SCL_1") (pintype "bidirectional"))
    )
    (net (code "49") (name "PB9") (class "Default")
      (node (ref "BRD1") (pin "31") (pinfunction "SDA_31") (pintype "bidirectional"))
      (node (ref "CON9") (pin "2") (pinfunction "TX/SDA_2") (pintype "bidirectional"))
      (node (ref "IC4") (pin "5") (pinfunction "SDA_5") (pintype "bidirectional"))
      (node (ref "MOD1") (pin "18") (pinfunction "PB9/SDA1_18") (pintype "bidirectional"))
      (node (ref "R11") (pin "1") (pinfunction "P$1_1") (pintype "passive"))
      (node (ref "R21") (pin "2") (pinfunction "P$2_2") (pintype "passive"))
      (node (ref "U2") (pin "6") (pinfunction "SDA_6") (pintype "bidirectional"))
      (node (ref "U4") (pin "1") (pinfunction "SDA_1") (pintype "bidirectional"))
      (node (ref "U5") (pin "6") (pinfunction "SDA_6") (pintype "bidirectional"))
    )
    (net (code "50") (name "PB10") (class "Default")
      (node (ref "BRD1") (pin "21") (pinfunction "D6_21") (pintype "bidirectional"))
      (node (ref "MOD1") (pin "19") (pinfunction "PB10_19") (pintype "bidirectional"))
      (node (ref "SW3") (pin "P$1") (pinfunction "P_P$1") (pintype "passive"))
    )
    (net (code "51") (name "PB12") (class "Default")
      (node (ref "BRD1") (pin "25") (pinfunction "D10/SS_25") (pintype "bidirectional"))
      (node (ref "CON4") (pin "4") (pinfunction "SEL_4") (pintype "bidirectional"))
      (node (ref "MOD1") (pin "5") (pinfunction "PB12/NSS2_5") (pintype "bidirectional"))
    )
    (net (code "52") (name "PB13") (class "Default")
      (node (ref "BRD1") (pin "28") (pinfunction "D13/SCK_28") (pintype "bidirectional"))
      (node (ref "CON4") (pin "1") (pinfunction "SCK_1") (pintype "bidirectional"))
      (node (ref "MOD1") (pin "6") (pinfunction "PB13/SCK2_6") (pintype "bidirectional"))
      (node (ref "U1") (pin "6") (pinfunction "SCK_6") (pintype "bidirectional"))
    )
    (net (code "53") (name "PB14") (class "Default")
      (node (ref "BRD1") (pin "27") (pinfunction "D12/MISO_27") (pintype "bidirectional"))
      (node (ref "CON4") (pin "2") (pinfunction "MISO_2") (pintype "bidirectional"))
      (node (ref "MOD1") (pin "7") (pinfunction "PB14/MISO2_7") (pintype "bidirectional"))
      (node (ref "U1") (pin "2") (pinfunction "SO_2") (pintype "bidirectional"))
    )
    (net (code "54") (name "PB15") (class "Default")
      (node (ref "BRD1") (pin "26") (pinfunction "D11/MOSI_26") (pintype "bidirectional"))
      (node (ref "CON4") (pin "3") (pinfunction "MOSI_3") (pintype "bidirectional"))
      (node (ref "MOD1") (pin "4") (pinfunction "PB15/MOSI2_4") (pintype "bidirectional"))
      (node (ref "U1") (pin "5") (pinfunction "SI_5") (pintype "bidirectional"))
    )
    (net (code "55") (name "PC0") (class "Default")
      (node (ref "BRD1") (pin "12") (pinfunction "A3_12") (pintype "bidirectional"))
      (node (ref "MOD1") (pin "14") (pinfunction "PC0_14") (pintype "bidirectional"))
    )
    (net (code "56") (name "PC6") (class "Default")
      (node (ref "BRD1") (pin "16") (pinfunction "D1/TX_16") (pintype "bidirectional"))
      (node (ref "MOD1") (pin "8") (pinfunction "PC6/TX6_8") (pintype "bidirectional"))
    )
    (net (code "57") (name "PC7") (class "Default")
      (node (ref "BRD1") (pin "15") (pinfunction "D0/RX_15") (pintype "bidirectional"))
      (node (ref "MOD1") (pin "12") (pinfunction "PC7/RX6_12") (pintype "bidirectional"))
    )
    (net (code "58") (name "PC13") (class "Default")
      (node (ref "BRD1") (pin "13") (pinfunction "A4_13") (pintype "bidirectional"))
      (node (ref "MOD1") (pin "16") (pinfunction "PC13_16") (pintype "bidirectional"))
    )
    (net (code "59") (name "TGT_NRESET") (class "Default")
      (node (ref "BRD1") (pin "3") (pinfunction "NRESET_3") (pintype "bidirectional"))
      (node (ref "C11") (pin "1") (pinfunction "P$1_1") (pintype "passive"))
      (node (ref "IC3") (pin "22") (pinfunction "TGT_NRESET_22") (pintype "bidirectional"))
      (node (ref "MOD1") (pin "13") (pinfunction "~{RESET}_13") (pintype "bidirectional"))
      (node (ref "R9") (pin "1") (pinfunction "P$1_1") (pintype "passive"))
    )
    (net (code "60") (name "TGT_NRST") (class "Default")
      (node (ref "IC3") (pin "21") (pinfunction "NRESET_FB_ISP_21") (pintype "bidirectional"))
      (node (ref "SW1") (pin "P$3") (pinfunction "B1_P$3") (pintype "passive"))
      (node (ref "SW1") (pin "P$4") (pinfunction "B2_P$4") (pintype "passive"))
    )
    (net (code "61") (name "TGT_RX") (class "Default")
      (node (ref "IC3") (pin "25") (pinfunction "TGT_RX_25") (pintype "bidirectional"))
      (node (ref "MOD1") (pin "29") (pinfunction "PB7/TGT_RX1_29") (pintype "bidirectional"))
    )
    (net (code "62") (name "TGT_SWCLK") (class "Default")
      (node (ref "IC3") (pin "26") (pinfunction "TGT_SWCLK_26") (pintype "bidirectional"))
      (node (ref "MOD1") (pin "25") (pinfunction "PA14/SWCLK_25") (pintype "bidirectional"))
    )
    (net (code "63") (name "TGT_SWDIO") (class "Default")
      (node (ref "IC3") (pin "27") (pinfunction "TGT_SWDIO_27") (pintype "bidirectional"))
      (node (ref "MOD1") (pin "26") (pinfunction "PA13/SWDIO_26") (pintype "bidirectional"))
    )
    (net (code "64") (name "TGT_TX") (class "Default")
      (node (ref "IC3") (pin "24") (pinfunction "TGT_TX_24") (pintype "bidirectional"))
      (node (ref "MOD1") (pin "30") (pinfunction "PB6/TGT_TX1_30") (pintype "bidirectional"))
    )
    (net (code "65") (name "USB-DM") (class "Default")
      (node (ref "IC2") (pin "6") (pinfunction "IO1_6") (pintype "bidirectional"))
      (node (ref "R2") (pin "2") (pinfunction "P$2_2") (pintype "passive"))
    )
    (net (code "66") (name "USB-DP") (class "Default")
      (node (ref "IC2") (pin "4") (pinfunction "IO2_4") (pintype "bidirectional"))
      (node (ref "R3") (pin "2") (pinfunction "P$2_2") (pintype "passive"))
    )
    (net (code "67") (name "unconnected-(BRD1-A5-Pad14)") (class "Default")
      (node (ref "BRD1") (pin "14") (pinfunction "A5_14") (pintype "bidirectional"))
    )
    (net (code "68") (name "unconnected-(BRD1-AREF-Pad30)") (class "Default")
      (node (ref "BRD1") (pin "30") (pinfunction "AREF_30") (pintype "bidirectional"))
    )
    (net (code "69") (name "unconnected-(BRD1-D7-Pad22)") (class "Default")
      (node (ref "BRD1") (pin "22") (pinfunction "D7_22") (pintype "bidirectional"))
    )
    (net (code "70") (name "unconnected-(BRD1-IOREF-Pad2)") (class "Default")
      (node (ref "BRD1") (pin "2") (pinfunction "IOREF_2") (pintype "bidirectional"))
    )
    (net (code "71") (name "unconnected-(BRD1-NC-Pad1)") (class "Default")
      (node (ref "BRD1") (pin "1") (pinfunction "NC_1") (pintype "bidirectional"))
    )
    (net (code "72") (name "unconnected-(CON3-NRESET-Pad3)") (class "Default")
      (node (ref "CON3") (pin "3") (pinfunction "NRESET_3") (pintype "passive"))
    )
    (net (code "73") (name "unconnected-(IC3-NC1-Pad9)") (class "Default")
      (node (ref "IC3") (pin "9") (pinfunction "NC1_9") (pintype "bidirectional"))
    )
    (net (code "74") (name "unconnected-(IC3-NC5-Pad11)") (class "Default")
      (node (ref "IC3") (pin "11") (pinfunction "NC5_11") (pintype "bidirectional"))
    )
    (net (code "75") (name "unconnected-(IC3-SLEEP_NREQ-Pad20)") (class "Default")
      (node (ref "IC3") (pin "20") (pinfunction "SLEEP_NREQ_20") (pintype "bidirectional"))
    )
    (net (code "76") (name "unconnected-(IC3-TGT_SWO-Pad28)") (class "Default")
      (node (ref "IC3") (pin "28") (pinfunction "TGT_SWO_28") (pintype "bidirectional"))
    )
    (net (code "77") (name "unconnected-(IC3-VOUT33-Pad5)") (class "Default")
      (node (ref "IC3") (pin "5") (pinfunction "VOUT33_5") (pintype "bidirectional"))
    )
    (net (code "78") (name "unconnected-(IC3-VREGIN-Pad6)") (class "Default")
      (node (ref "IC3") (pin "6") (pinfunction "VREGIN_6") (pintype "bidirectional"))
    )
    (net (code "79") (name "unconnected-(IC3-WAKE_NREQ-Pad23)") (class "Default")
      (node (ref "IC3") (pin "23") (pinfunction "WAKE_NREQ_23") (pintype "bidirectional"))
    )
    (net (code "80") (name "unconnected-(IC4-NC1-Pad1)") (class "Default")
      (node (ref "IC4") (pin "1") (pinfunction "NC1_1") (pintype "bidirectional"))
    )
    (net (code "81") (name "unconnected-(IC4-NC2-Pad2)") (class "Default")
      (node (ref "IC4") (pin "2") (pinfunction "NC2_2") (pintype "bidirectional"))
    )
    (net (code "82") (name "unconnected-(IC4-NC3-Pad3)") (class "Default")
      (node (ref "IC4") (pin "3") (pinfunction "NC3_3") (pintype "bidirectional"))
    )
    (net (code "83") (name "unconnected-(IC4-NC7-Pad7)") (class "Default")
      (node (ref "IC4") (pin "7") (pinfunction "NC7_7") (pintype "bidirectional"))
    )
    (net (code "84") (name "unconnected-(MOD1-ANT-Pad41)") (class "Default")
      (node (ref "MOD1") (pin "41") (pinfunction "ANT_41") (pintype "bidirectional"))
    )
    (net (code "85") (name "unconnected-(U4-ALERT-Pad3)") (class "Default")
      (node (ref "U4") (pin "3") (pinfunction "ALERT_3") (pintype "bidirectional"))
    )
    (net (code "86") (name "unconnected-(U4-~{RESET}-Pad6)") (class "Default")
      (node (ref "U4") (pin "6") (pinfunction "~{RESET}_6") (pintype "bidirectional"))
    )
  )
)
